# RC_car.net
KiCad netlist of a schematic drawn in EasyEDA
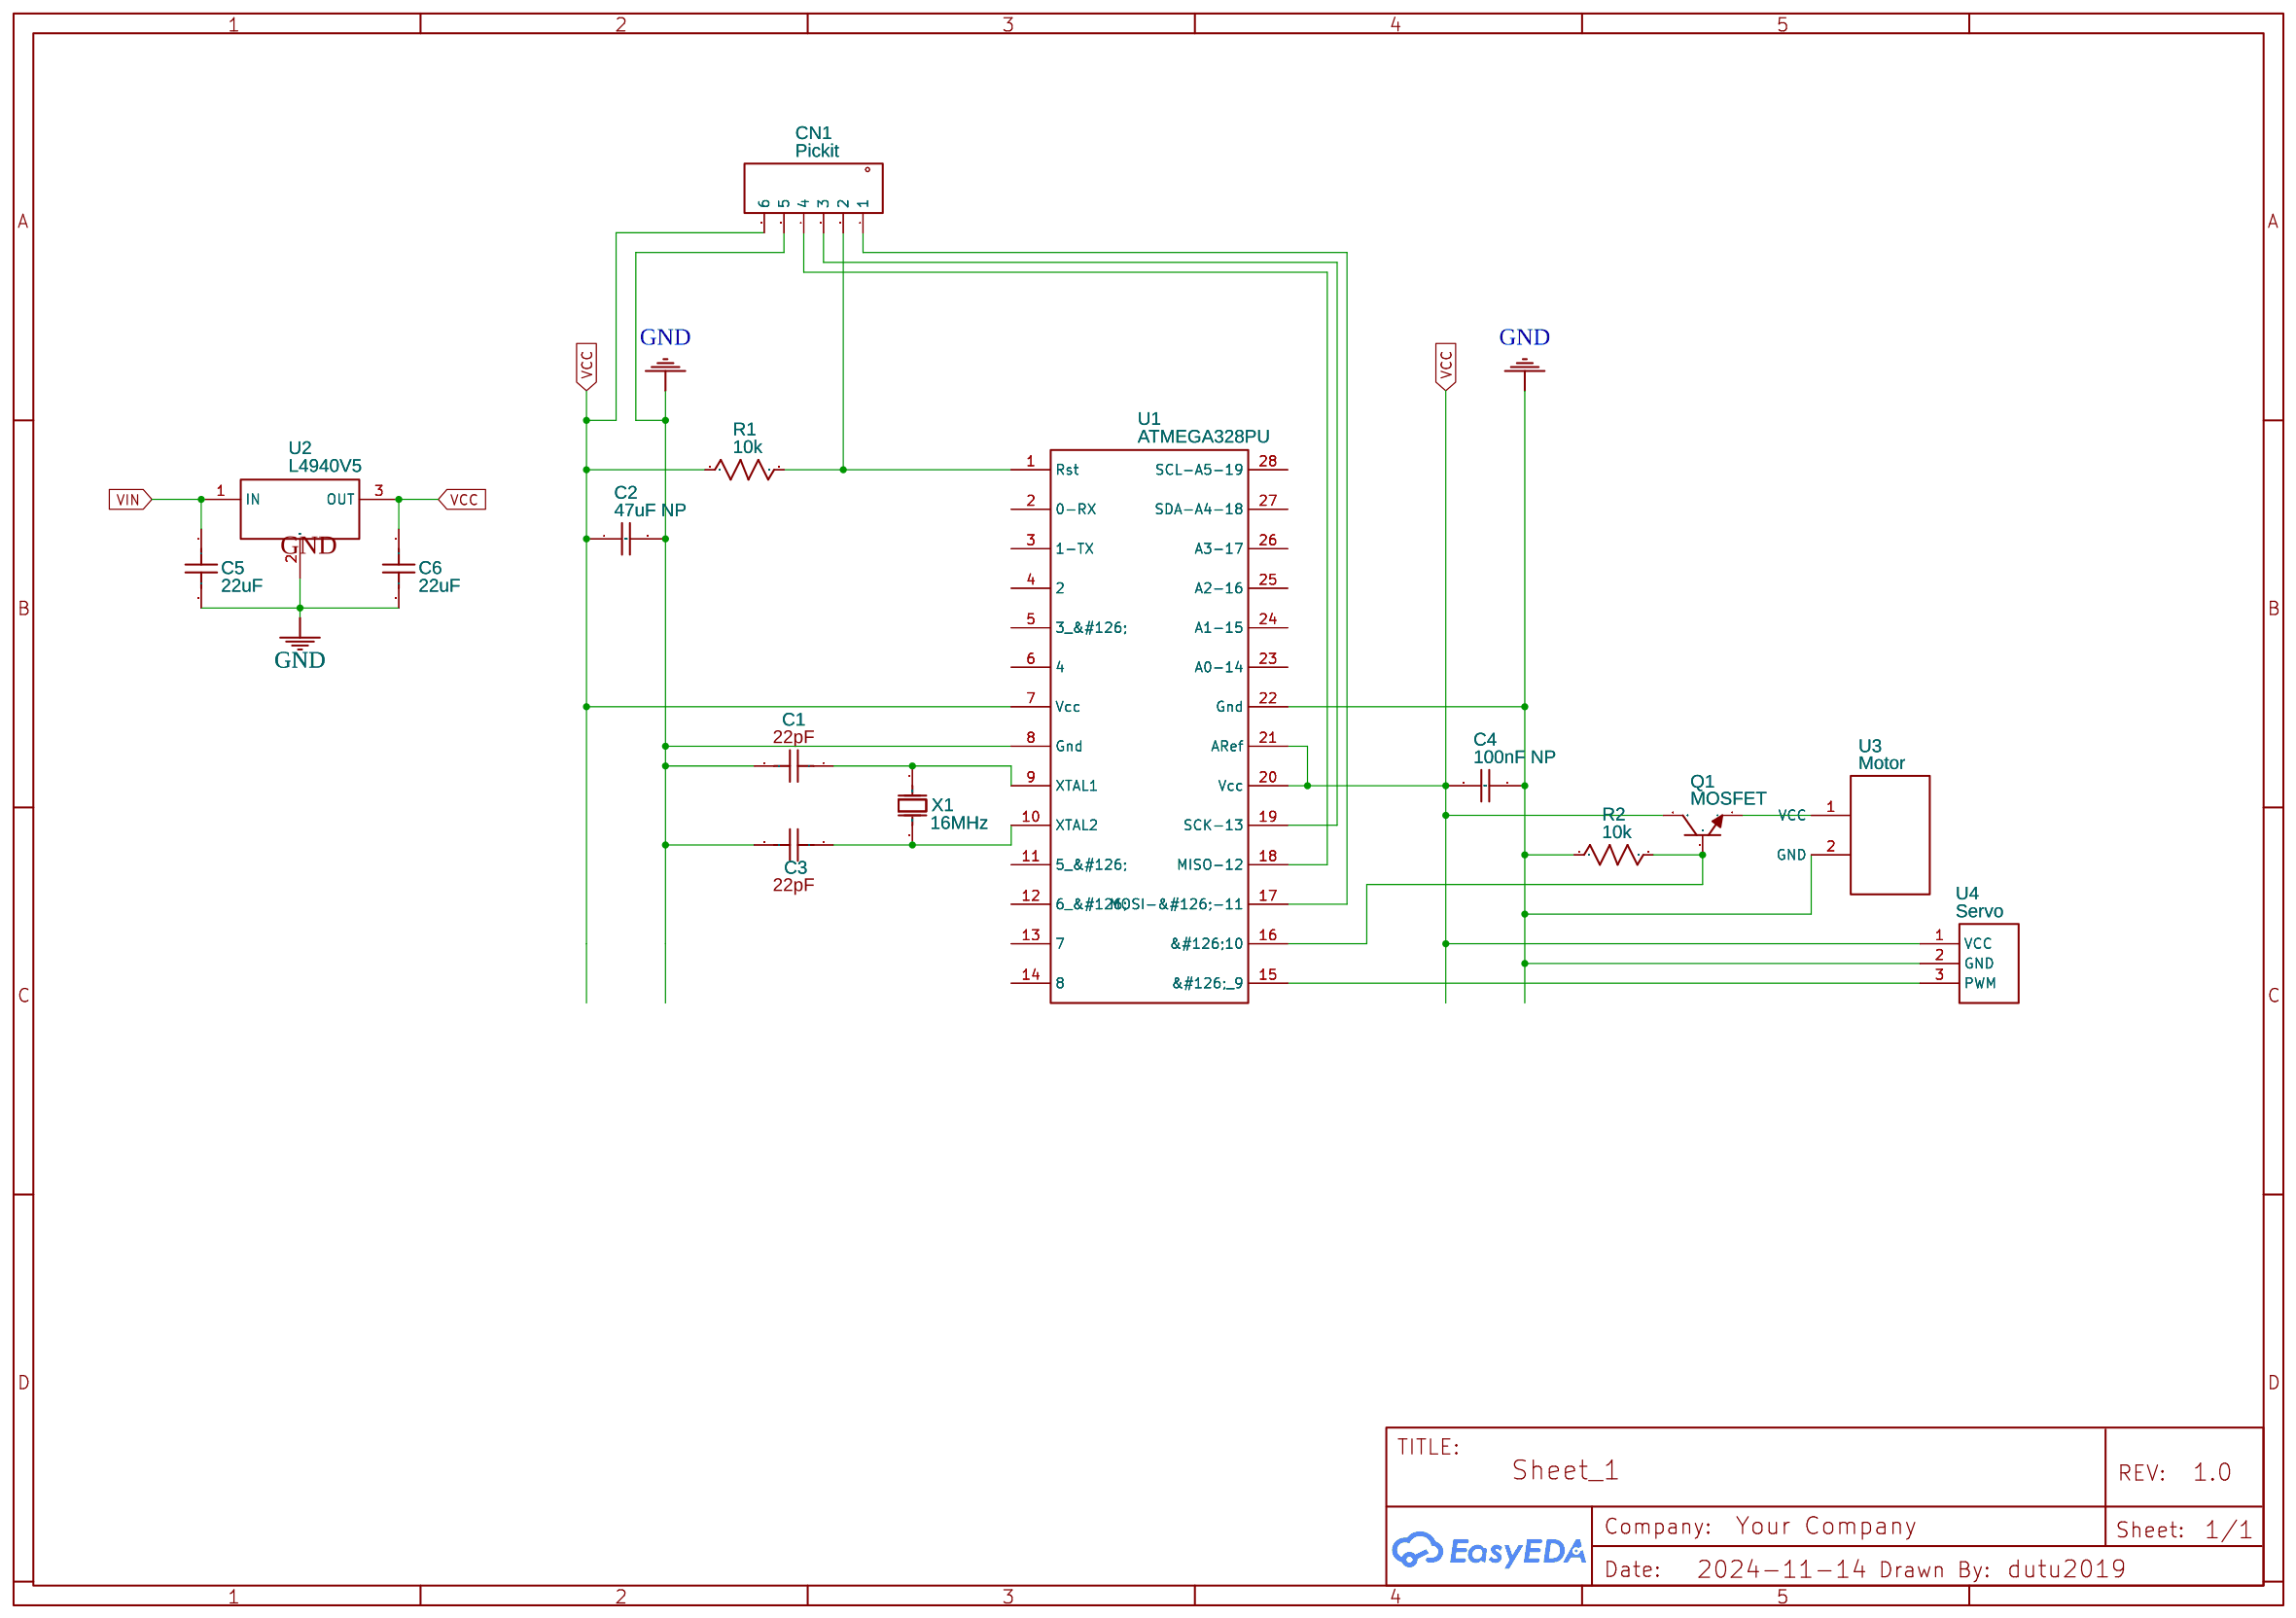
[diagram p0: schematic sheet]

(export (version "E")
  (design (tool "Eeschema 10.0.6"))
  (components
    (comp (ref "C1") (value "22pF Ceramic Capacitor") (libsource (lib "") (part "22pF Ceramic Capacitor")))
    (comp (ref "C2") (value "47uF NP") (libsource (lib "") (part "104 Non-Polarized Capacitor [1] 1")))
    (comp (ref "C3") (value "22pF Ceramic Capacitor") (libsource (lib "") (part "22pF Ceramic Capacitor_1")))
    (comp (ref "C4") (value "100nF NP") (libsource (lib "") (part "104 Non-Polarized Capacitor [1] 1")))
    (comp (ref "C5") (value "22uF") (libsource (lib "") (part "C_0603_US")))
    (comp (ref "C6") (value "22uF") (libsource (lib "") (part "C_0603_US")))
    (comp (ref "CN1") (value "Pickit") (libsource (lib "") (part "PINHEADER-6PIN6")))
    (comp (ref "Q1")
      (value "MOSFET")
      (fields (field (name "Manufacturer Part") "2n3904S-RTK/PS") (field (name "Manufacturer") "KEC"))
      (libsource (lib "") (part "2N3904(SOT-23)"))
    )
    (comp (ref "R1") (value "10k") (libsource (lib "") (part "R_0603_US")))
    (comp (ref "R2") (value "10k") (libsource (lib "") (part "R_0603_US")))
    (comp (ref "U1") (value "ATMEGA328PU") (libsource (lib "") (part "ATMEGA328PU")))
    (comp (ref "U2")
      (value "L4940V5")
      (fields (field (name "Manufacturer") "ST(意法半导体)"))
      (libsource (lib "") (part "L4940V5"))
    )
    (comp (ref "U3") (value "Motor") (libsource (lib "") (part "2-pin header")))
    (comp (ref "U4") (value "Servo") (libsource (lib "") (part "3-PIN HEADER")))
    (comp (ref "X1")
      (value "16MHz")
      (fields (field (name "Manufacturer Part") "9B-48.000MAAE-B") (field (name "Manufacturer") "TXC"))
      (libsource (lib "") (part "CRISTAL_16MHZ COPY"))
    )
  )
  (nets
    (net (code "1") (name "GND") (class "Default")
      (node (ref "C1") (pin "2") (pinfunction "2_2") (pintype "unspecified"))
      (node (ref "C2") (pin "2") (pinfunction "2_2") (pintype "unspecified"))
      (node (ref "C3") (pin "2") (pinfunction "2_2") (pintype "unspecified"))
      (node (ref "C4") (pin "2") (pinfunction "2_2") (pintype "unspecified"))
      (node (ref "C5") (pin "2") (pinfunction "2_2") (pintype "unspecified"))
      (node (ref "C6") (pin "2") (pinfunction "2_2") (pintype "unspecified"))
      (node (ref "CN1") (pin "5") (pinfunction "5_5") (pintype "input"))
      (node (ref "R2") (pin "1") (pinfunction "1_1") (pintype "unspecified"))
      (node (ref "U1") (pin "22") (pinfunction "Gnd_22") (pintype "unspecified"))
      (node (ref "U1") (pin "8") (pinfunction "Gnd_8") (pintype "unspecified"))
      (node (ref "U2") (pin "2") (pinfunction "GND_2") (pintype "passive"))
      (node (ref "U4") (pin "2") (pinfunction "GND_2") (pintype "unspecified"))
    )
    (net (code "2") (name "Net-(Q1-B)") (class "Default")
      (node (ref "Q1") (pin "2") (pinfunction "B_2") (pintype "input"))
      (node (ref "R2") (pin "2") (pinfunction "2_2") (pintype "unspecified"))
      (node (ref "U1") (pin "16") (pinfunction "&#126;10_16") (pintype "unspecified"))
    )
    (net (code "3") (name "Net-(Q1-E)") (class "Default")
      (node (ref "Q1") (pin "1") (pinfunction "E_1") (pintype "input"))
      (node (ref "U3") (pin "1") (pinfunction "VCC_1") (pintype "unspecified"))
    )
    (net (code "4") (name "Net-(U1-&#126;_9)") (class "Default")
      (node (ref "U1") (pin "15") (pinfunction "&#126;_9_15") (pintype "unspecified"))
      (node (ref "U4") (pin "3") (pinfunction "PWM_3") (pintype "unspecified"))
    )
    (net (code "5") (name "Net-(U1-MISO-12)") (class "Default")
      (node (ref "CN1") (pin "4") (pinfunction "4_4") (pintype "input"))
      (node (ref "U1") (pin "18") (pinfunction "MISO-12_18") (pintype "unspecified"))
    )
    (net (code "6") (name "Net-(U1-MOSI-&#126;-11)") (class "Default")
      (node (ref "CN1") (pin "1") (pinfunction "1_1") (pintype "input"))
      (node (ref "U1") (pin "17") (pinfunction "MOSI-&#126;-11_17") (pintype "unspecified"))
    )
    (net (code "7") (name "Net-(U1-Rst)") (class "Default")
      (node (ref "CN1") (pin "2") (pinfunction "2_2") (pintype "input"))
      (node (ref "R1") (pin "2") (pinfunction "2_2") (pintype "unspecified"))
      (node (ref "U1") (pin "1") (pinfunction "Rst_1") (pintype "unspecified"))
    )
    (net (code "8") (name "Net-(U1-SCK-13)") (class "Default")
      (node (ref "CN1") (pin "3") (pinfunction "3_3") (pintype "input"))
      (node (ref "U1") (pin "19") (pinfunction "SCK-13_19") (pintype "unspecified"))
    )
    (net (code "9") (name "Net-(U1-XTAL1)") (class "Default")
      (node (ref "C1") (pin "1") (pinfunction "1_1") (pintype "unspecified"))
      (node (ref "U1") (pin "9") (pinfunction "XTAL1_9") (pintype "unspecified"))
      (node (ref "X1") (pin "1") (pinfunction "OSC1_1") (pintype "input"))
    )
    (net (code "10") (name "Net-(U1-XTAL2)") (class "Default")
      (node (ref "C3") (pin "1") (pinfunction "1_1") (pintype "unspecified"))
      (node (ref "U1") (pin "10") (pinfunction "XTAL2_10") (pintype "unspecified"))
      (node (ref "X1") (pin "2") (pinfunction "OSC2_2") (pintype "input"))
    )
    (net (code "11") (name "VCC") (class "Default")
      (node (ref "C2") (pin "1") (pinfunction "1_1") (pintype "unspecified"))
      (node (ref "C4") (pin "1") (pinfunction "1_1") (pintype "unspecified"))
      (node (ref "C6") (pin "1") (pinfunction "1_1") (pintype "unspecified"))
      (node (ref "CN1") (pin "6") (pinfunction "6_6") (pintype "input"))
      (node (ref "Q1") (pin "3") (pinfunction "C_3") (pintype "input"))
      (node (ref "R1") (pin "1") (pinfunction "1_1") (pintype "unspecified"))
      (node (ref "U1") (pin "20") (pinfunction "Vcc_20") (pintype "unspecified"))
      (node (ref "U1") (pin "21") (pinfunction "ARef_21") (pintype "unspecified"))
      (node (ref "U1") (pin "7") (pinfunction "Vcc_7") (pintype "unspecified"))
      (node (ref "U2") (pin "3") (pinfunction "OUT_3") (pintype "passive"))
      (node (ref "U4") (pin "1") (pinfunction "VCC_1") (pintype "unspecified"))
    )
    (net (code "12") (name "VIN") (class "Default")
      (node (ref "C5") (pin "1") (pinfunction "1_1") (pintype "unspecified"))
      (node (ref "U2") (pin "1") (pinfunction "IN_1") (pintype "passive"))
    )
    (net (code "13") (name "unconnected-(U1-0-RX-Pad2)") (class "Default")
      (node (ref "U1") (pin "2") (pinfunction "0-RX_2") (pintype "unspecified"))
    )
    (net (code "14") (name "unconnected-(U1-1-TX-Pad3)") (class "Default")
      (node (ref "U1") (pin "3") (pinfunction "1-TX_3") (pintype "unspecified"))
    )
    (net (code "15") (name "unconnected-(U1-2-Pad4)") (class "Default")
      (node (ref "U1") (pin "4") (pinfunction "2_4") (pintype "unspecified"))
    )
    (net (code "16") (name "unconnected-(U1-3_&#126;-Pad5)") (class "Default")
      (node (ref "U1") (pin "5") (pinfunction "3_&#126;_5") (pintype "unspecified"))
    )
    (net (code "17") (name "unconnected-(U1-4-Pad6)") (class "Default")
      (node (ref "U1") (pin "6") (pinfunction "4_6") (pintype "unspecified"))
    )
    (net (code "18") (name "unconnected-(U1-5_&#126;-Pad11)") (class "Default")
      (node (ref "U1") (pin "11") (pinfunction "5_&#126;_11") (pintype "unspecified"))
    )
    (net (code "19") (name "unconnected-(U1-6_&#126;-Pad12)") (class "Default")
      (node (ref "U1") (pin "12") (pinfunction "6_&#126;_12") (pintype "unspecified"))
    )
    (net (code "20") (name "unconnected-(U1-7-Pad13)") (class "Default")
      (node (ref "U1") (pin "13") (pinfunction "7_13") (pintype "unspecified"))
    )
    (net (code "21") (name "unconnected-(U1-8-Pad14)") (class "Default")
      (node (ref "U1") (pin "14") (pinfunction "8_14") (pintype "unspecified"))
    )
    (net (code "22") (name "unconnected-(U1-A0-14-Pad23)") (class "Default")
      (node (ref "U1") (pin "23") (pinfunction "A0-14_23") (pintype "unspecified"))
    )
    (net (code "23") (name "unconnected-(U1-A1-15-Pad24)") (class "Default")
      (node (ref "U1") (pin "24") (pinfunction "A1-15_24") (pintype "unspecified"))
    )
    (net (code "24") (name "unconnected-(U1-A2-16-Pad25)") (class "Default")
      (node (ref "U1") (pin "25") (pinfunction "A2-16_25") (pintype "unspecified"))
    )
    (net (code "25") (name "unconnected-(U1-A3-17-Pad26)") (class "Default")
      (node (ref "U1") (pin "26") (pinfunction "A3-17_26") (pintype "unspecified"))
    )
    (net (code "26") (name "unconnected-(U1-SCL-A5-19-Pad28)") (class "Default")
      (node (ref "U1") (pin "28") (pinfunction "SCL-A5-19_28") (pintype "unspecified"))
    )
    (net (code "27") (name "unconnected-(U1-SDA-A4-18-Pad27)") (class "Default")
      (node (ref "U1") (pin "27") (pinfunction "SDA-A4-18_27") (pintype "unspecified"))
    )
    (net (code "28") (name "unconnected-(U3-GND-Pad2)") (class "Default")
      (node (ref "U3") (pin "2") (pinfunction "GND_2") (pintype "unspecified"))
    )
  )
)
